# Adafruit_128x64_Mono_OLED_PCB.net
KiCad netlist of a schematic drawn in EAGLE
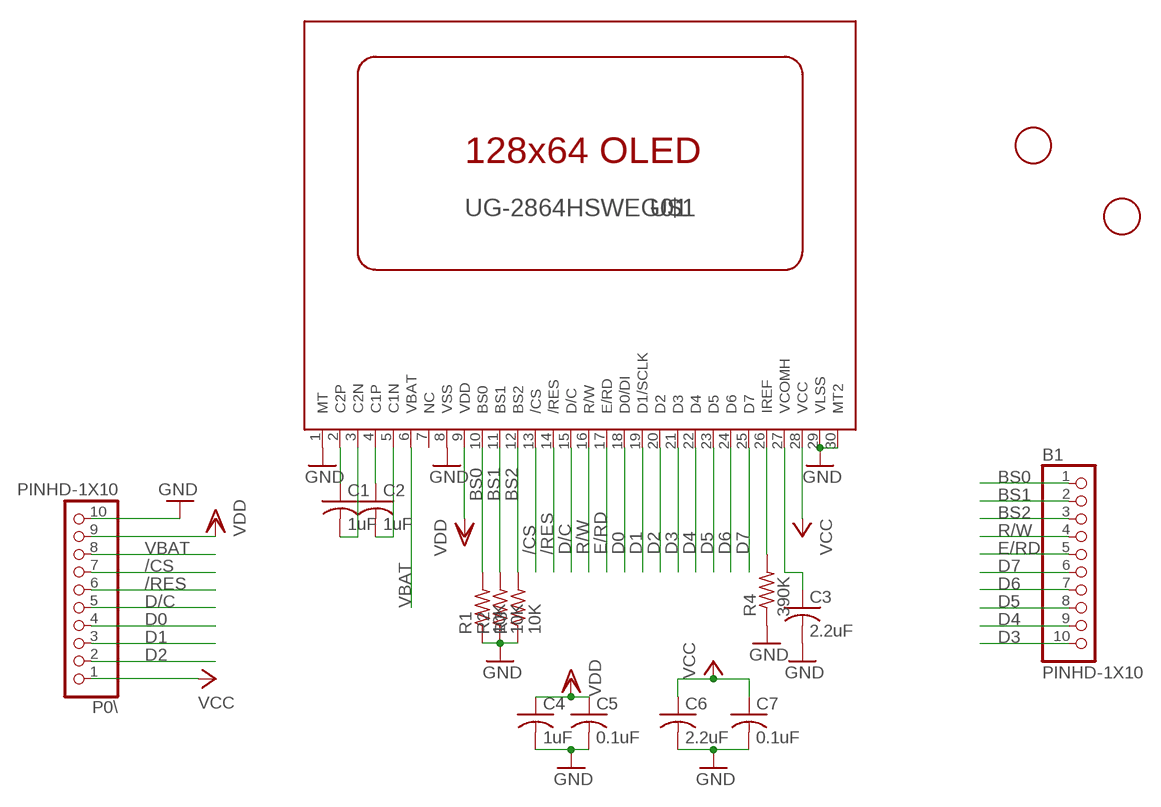
[diagram p0: schematic, sheet 1]

(export (version "E")
  (design (tool "Eeschema 10.0.6"))
  (components
    (comp (ref "B1")
      (value "PINHD-1X10")
      (footprint "eagle-import:1X10-BIG")
      (libsource (lib "eagle-import") (part "PINHD-1X10"))
    )
    (comp (ref "C1")
      (value "1uF")
      (footprint "eagle-import:C0805K")
      (libsource (lib "eagle-import") (part "C-USC0805K"))
    )
    (comp (ref "C2")
      (value "1uF")
      (footprint "eagle-import:C0805K")
      (libsource (lib "eagle-import") (part "C-USC0805K"))
    )
    (comp (ref "C3")
      (value "2.2uF")
      (footprint "eagle-import:C0805K")
      (libsource (lib "eagle-import") (part "C-USC0805K"))
    )
    (comp (ref "C4")
      (value "1uF")
      (footprint "eagle-import:C0805K")
      (libsource (lib "eagle-import") (part "C-USC0805K"))
    )
    (comp (ref "C5")
      (value "0.1uF")
      (footprint "eagle-import:C0805K")
      (libsource (lib "eagle-import") (part "C-USC0805K"))
    )
    (comp (ref "C6")
      (value "2.2uF")
      (footprint "eagle-import:C0805K")
      (libsource (lib "eagle-import") (part "C-USC0805K"))
    )
    (comp (ref "C7")
      (value "0.1uF")
      (footprint "eagle-import:C0805K")
      (libsource (lib "eagle-import") (part "C-USC0805K"))
    )
    (comp (ref "P0\\")
      (value "PINHD-1X10")
      (footprint "eagle-import:1X10-BIG")
      (libsource (lib "eagle-import") (part "PINHD-1X10"))
    )
    (comp (ref "R1")
      (value "10K")
      (footprint "eagle-import:R0805")
      (libsource (lib "eagle-import") (part "R-US_R0805"))
    )
    (comp (ref "R2")
      (value "10K")
      (footprint "eagle-import:R0805")
      (libsource (lib "eagle-import") (part "R-US_R0805"))
    )
    (comp (ref "R3")
      (value "10K")
      (footprint "eagle-import:R0805")
      (libsource (lib "eagle-import") (part "R-US_R0805"))
    )
    (comp (ref "R4")
      (value "390K")
      (footprint "eagle-import:R0805")
      (libsource (lib "eagle-import") (part "R-US_R0805"))
    )
    (comp (ref "U$1")
      (value "UG-2864HSWEG01")
      (footprint "eagle-import:1X30-0.7MM")
      (libsource (lib "eagle-import") (part "UG-2864HSWEG01"))
    )
    (comp (ref "U$3")
      (value "FIDUCIAL")
      (footprint "eagle-import:FIDUCIAL_1MM")
      (libsource (lib "eagle-import") (part "FIDUCIAL"))
    )
    (comp (ref "U$4")
      (value "FIDUCIAL")
      (footprint "eagle-import:FIDUCIAL_1MM")
      (libsource (lib "eagle-import") (part "FIDUCIAL"))
    )
  )
  (nets
    (net (code "1") (name "/BS0") (class "Default")
      (node (ref "B1") (pin "1") (pinfunction "1_1") (pintype "passive"))
      (node (ref "R1") (pin "2") (pinfunction "2_2") (pintype "passive"))
      (node (ref "U$1") (pin "10") (pinfunction "BS0_10") (pintype "input"))
    )
    (net (code "2") (name "/BS1") (class "Default")
      (node (ref "B1") (pin "2") (pinfunction "2_2") (pintype "passive"))
      (node (ref "R2") (pin "2") (pinfunction "2_2") (pintype "passive"))
      (node (ref "U$1") (pin "11") (pinfunction "BS1_11") (pintype "input"))
    )
    (net (code "3") (name "/BS2") (class "Default")
      (node (ref "B1") (pin "3") (pinfunction "3_3") (pintype "passive"))
      (node (ref "R3") (pin "2") (pinfunction "2_2") (pintype "passive"))
      (node (ref "U$1") (pin "12") (pinfunction "BS2_12") (pintype "input"))
    )
    (net (code "4") (name "/D0") (class "Default")
      (node (ref "P0\\") (pin "4") (pinfunction "4_4") (pintype "passive"))
      (node (ref "U$1") (pin "18") (pinfunction "D0/DI_18") (pintype "bidirectional"))
    )
    (net (code "5") (name "/D1") (class "Default")
      (node (ref "P0\\") (pin "3") (pinfunction "3_3") (pintype "passive"))
      (node (ref "U$1") (pin "19") (pinfunction "D1/SCLK_19") (pintype "bidirectional"))
    )
    (net (code "6") (name "/D2") (class "Default")
      (node (ref "P0\\") (pin "2") (pinfunction "2_2") (pintype "passive"))
      (node (ref "U$1") (pin "20") (pinfunction "D2_20") (pintype "bidirectional"))
    )
    (net (code "7") (name "/D3") (class "Default")
      (node (ref "B1") (pin "10") (pinfunction "10_10") (pintype "passive"))
      (node (ref "U$1") (pin "21") (pinfunction "D3_21") (pintype "bidirectional"))
    )
    (net (code "8") (name "/D4") (class "Default")
      (node (ref "B1") (pin "9") (pinfunction "9_9") (pintype "passive"))
      (node (ref "U$1") (pin "22") (pinfunction "D4_22") (pintype "bidirectional"))
    )
    (net (code "9") (name "/D5") (class "Default")
      (node (ref "B1") (pin "8") (pinfunction "8_8") (pintype "passive"))
      (node (ref "U$1") (pin "23") (pinfunction "D5_23") (pintype "bidirectional"))
    )
    (net (code "10") (name "/D6") (class "Default")
      (node (ref "B1") (pin "7") (pinfunction "7_7") (pintype "passive"))
      (node (ref "U$1") (pin "24") (pinfunction "D6_24") (pintype "bidirectional"))
    )
    (net (code "11") (name "/D7") (class "Default")
      (node (ref "B1") (pin "6") (pinfunction "6_6") (pintype "passive"))
      (node (ref "U$1") (pin "25") (pinfunction "D7_25") (pintype "bidirectional"))
    )
    (net (code "12") (name "/D{slash}C") (class "Default")
      (node (ref "P0\\") (pin "5") (pinfunction "5_5") (pintype "passive"))
      (node (ref "U$1") (pin "15") (pinfunction "D/C_15") (pintype "input"))
    )
    (net (code "13") (name "/E{slash}RD") (class "Default")
      (node (ref "B1") (pin "5") (pinfunction "5_5") (pintype "passive"))
      (node (ref "U$1") (pin "17") (pinfunction "E/RD_17") (pintype "input"))
    )
    (net (code "14") (name "/R{slash}W") (class "Default")
      (node (ref "B1") (pin "4") (pinfunction "4_4") (pintype "passive"))
      (node (ref "U$1") (pin "16") (pinfunction "R/W_16") (pintype "input"))
    )
    (net (code "15") (name "/VBAT") (class "Default")
      (node (ref "P0\\") (pin "8") (pinfunction "8_8") (pintype "passive"))
      (node (ref "U$1") (pin "6") (pinfunction "VBAT_6") (pintype "input"))
    )
    (net (code "16") (name "/{slash}CS") (class "Default")
      (node (ref "P0\\") (pin "7") (pinfunction "7_7") (pintype "passive"))
      (node (ref "U$1") (pin "13") (pinfunction "/CS_13") (pintype "input"))
    )
    (net (code "17") (name "/{slash}RES") (class "Default")
      (node (ref "P0\\") (pin "6") (pinfunction "6_6") (pintype "passive"))
      (node (ref "U$1") (pin "14") (pinfunction "/RES_14") (pintype "input"))
    )
    (net (code "18") (name "GND") (class "Default")
      (node (ref "C3") (pin "2") (pinfunction "2_2") (pintype "passive"))
      (node (ref "C4") (pin "2") (pinfunction "2_2") (pintype "passive"))
      (node (ref "C5") (pin "2") (pinfunction "2_2") (pintype "passive"))
      (node (ref "C6") (pin "2") (pinfunction "2_2") (pintype "passive"))
      (node (ref "C7") (pin "2") (pinfunction "2_2") (pintype "passive"))
      (node (ref "P0\\") (pin "10") (pinfunction "10_10") (pintype "passive"))
      (node (ref "R1") (pin "1") (pinfunction "1_1") (pintype "passive"))
      (node (ref "R2") (pin "1") (pinfunction "1_1") (pintype "passive"))
      (node (ref "R3") (pin "1") (pinfunction "1_1") (pintype "passive"))
      (node (ref "R4") (pin "1") (pinfunction "1_1") (pintype "passive"))
      (node (ref "U$1") (pin "1") (pinfunction "MT_1") (pintype "input"))
      (node (ref "U$1") (pin "29") (pinfunction "VLSS_29") (pintype "power_in"))
      (node (ref "U$1") (pin "30") (pinfunction "MT2_30") (pintype "input"))
      (node (ref "U$1") (pin "8") (pinfunction "VSS_8") (pintype "power_in"))
    )
    (net (code "19") (name "Net-(U$1-C1N)") (class "Default")
      (node (ref "C2") (pin "2") (pinfunction "2_2") (pintype "passive"))
      (node (ref "U$1") (pin "5") (pinfunction "C1N_5") (pintype "input"))
    )
    (net (code "20") (name "Net-(U$1-C1P)") (class "Default")
      (node (ref "C2") (pin "1") (pinfunction "1_1") (pintype "passive"))
      (node (ref "U$1") (pin "4") (pinfunction "C1P_4") (pintype "input"))
    )
    (net (code "21") (name "Net-(U$1-C2N)") (class "Default")
      (node (ref "C1") (pin "2") (pinfunction "2_2") (pintype "passive"))
      (node (ref "U$1") (pin "3") (pinfunction "C2N_3") (pintype "input"))
    )
    (net (code "22") (name "Net-(U$1-C2P)") (class "Default")
      (node (ref "C1") (pin "1") (pinfunction "1_1") (pintype "passive"))
      (node (ref "U$1") (pin "2") (pinfunction "C2P_2") (pintype "input"))
    )
    (net (code "23") (name "Net-(U$1-IREF)") (class "Default")
      (node (ref "R4") (pin "2") (pinfunction "2_2") (pintype "passive"))
      (node (ref "U$1") (pin "26") (pinfunction "IREF_26") (pintype "input"))
    )
    (net (code "24") (name "Net-(U$1-VCOMH)") (class "Default")
      (node (ref "C3") (pin "1") (pinfunction "1_1") (pintype "passive"))
      (node (ref "U$1") (pin "27") (pinfunction "VCOMH_27") (pintype "output"))
    )
    (net (code "25") (name "VCC") (class "Default")
      (node (ref "C6") (pin "1") (pinfunction "1_1") (pintype "passive"))
      (node (ref "C7") (pin "1") (pinfunction "1_1") (pintype "passive"))
      (node (ref "P0\\") (pin "1") (pinfunction "1_1") (pintype "passive"))
      (node (ref "U$1") (pin "28") (pinfunction "VCC_28") (pintype "power_in"))
    )
    (net (code "26") (name "VDD") (class "Default")
      (node (ref "C4") (pin "1") (pinfunction "1_1") (pintype "passive"))
      (node (ref "C5") (pin "1") (pinfunction "1_1") (pintype "passive"))
      (node (ref "P0\\") (pin "9") (pinfunction "9_9") (pintype "passive"))
      (node (ref "U$1") (pin "9") (pinfunction "VDD_9") (pintype "power_in"))
    )
    (net (code "27") (name "unconnected-(U$1-NC-Pad7)") (class "Default")
      (node (ref "U$1") (pin "7") (pinfunction "NC_7") (pintype "no_connect"))
    )
  )
)
